# SENSE_AMP.net
KiCad netlist of a schematic drawn in Altium Designer
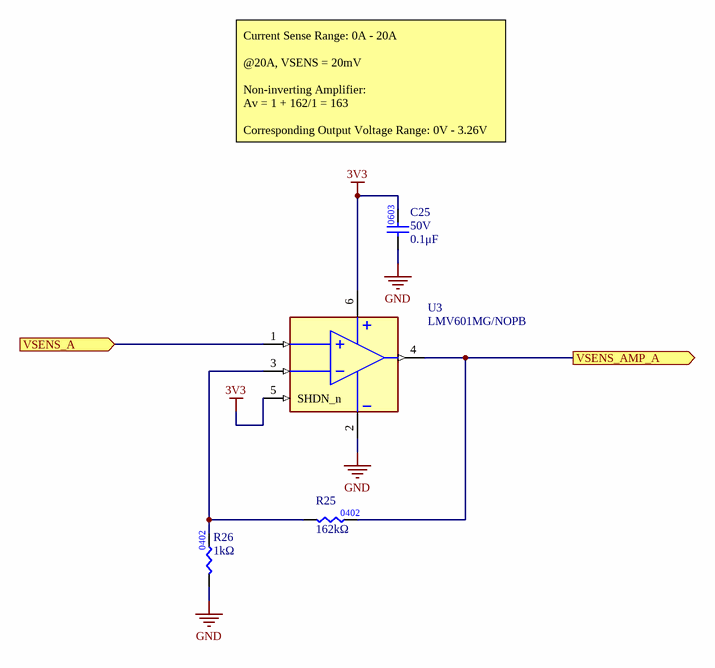
[diagram p0: SENSE_AMP.SchDoc]

(export (version "E")
  (design (tool "Eeschema 10.0.6"))
  (components
    (comp (ref "C25")
      (value "0.1μF")
      (footprint "CAP0603")
      (description "CAP CER 0.1UF 50V X7R 0603")
      (fields (field (name "VOLTAGE RATING") "50V") (field (name "Comment") "CAP_0.1uF_50V_0603"))
      (libsource (lib "UWRT_Schematic_Library_2020") (part "CAP_0.1uF_50V_0603"))
    )
    (comp (ref "R25")
      (value "162kΩ")
      (footprint "RES0402")
      (description "RES 162K OHM 1% 1/16W 0402")
      (fields (field (name "POWER") "0.063W, 1/16W") (field (name "TOLERANCE") "1%"))
      (libsource (lib "UWRT_Schematic_Library_2020") (part "RES_162kΩ_0402_1%"))
    )
    (comp (ref "R26")
      (value "1kΩ")
      (footprint "RES0402")
      (description "RES 1K OHM 1% 1/16W 0402")
      (fields (field (name "TOLERANCE") "1%") (field (name "Comment") "RES_1kΩ_0402_1%"))
      (libsource (lib "UWRT_Schematic_Library_2020") (part "RES_1kΩ_0402_1%"))
    )
    (comp (ref "U3")
      (value "LMV601MG/NOPB")
      (footprint "SOT65P210X110-6N")
      (description "IC OPAMP GP 1 CIRCUIT SC70-6")
      (fields (field (name "MANUFACTURER") "Texas Instruments"))
      (libsource (lib "UWRT_Schematic_Library_2020") (part "IC_OPAMP_GP"))
    )
  )
  (nets
    (net (code "1") (name "/VSENS_A") (class "Default")
      (node (ref "U3") (pin "1") (pinfunction "IN+_1") (pintype "input"))
    )
    (net (code "2") (name "/VSENS_AMP_A") (class "Default")
      (node (ref "R25") (pin "2") (pinfunction "2_2") (pintype "passive"))
      (node (ref "U3") (pin "4") (pinfunction "OUT_4") (pintype "output"))
    )
    (net (code "3") (name "3V3") (class "Default")
      (node (ref "C25") (pin "2") (pinfunction "2_2") (pintype "passive"))
      (node (ref "U3") (pin "5") (pinfunction "SHDN_n_5") (pintype "input"))
      (node (ref "U3") (pin "6") (pinfunction "V+_6") (pintype "power_in"))
    )
    (net (code "4") (name "GND") (class "Default")
      (node (ref "C25") (pin "1") (pinfunction "1_1") (pintype "passive"))
      (node (ref "R26") (pin "1") (pinfunction "1_1") (pintype "passive"))
      (node (ref "U3") (pin "2") (pinfunction "GND_2") (pintype "power_in"))
    )
    (net (code "5") (name "Net-(U3-IN-)") (class "Default")
      (node (ref "R25") (pin "1") (pinfunction "1_1") (pintype "passive"))
      (node (ref "R26") (pin "2") (pinfunction "2_2") (pintype "passive"))
      (node (ref "U3") (pin "3") (pinfunction "IN-_3") (pintype "input"))
    )
  )
)
